# mp3412-boost-driver-17mm-mk-2_0.net
KiCad netlist of a schematic drawn in EAGLE
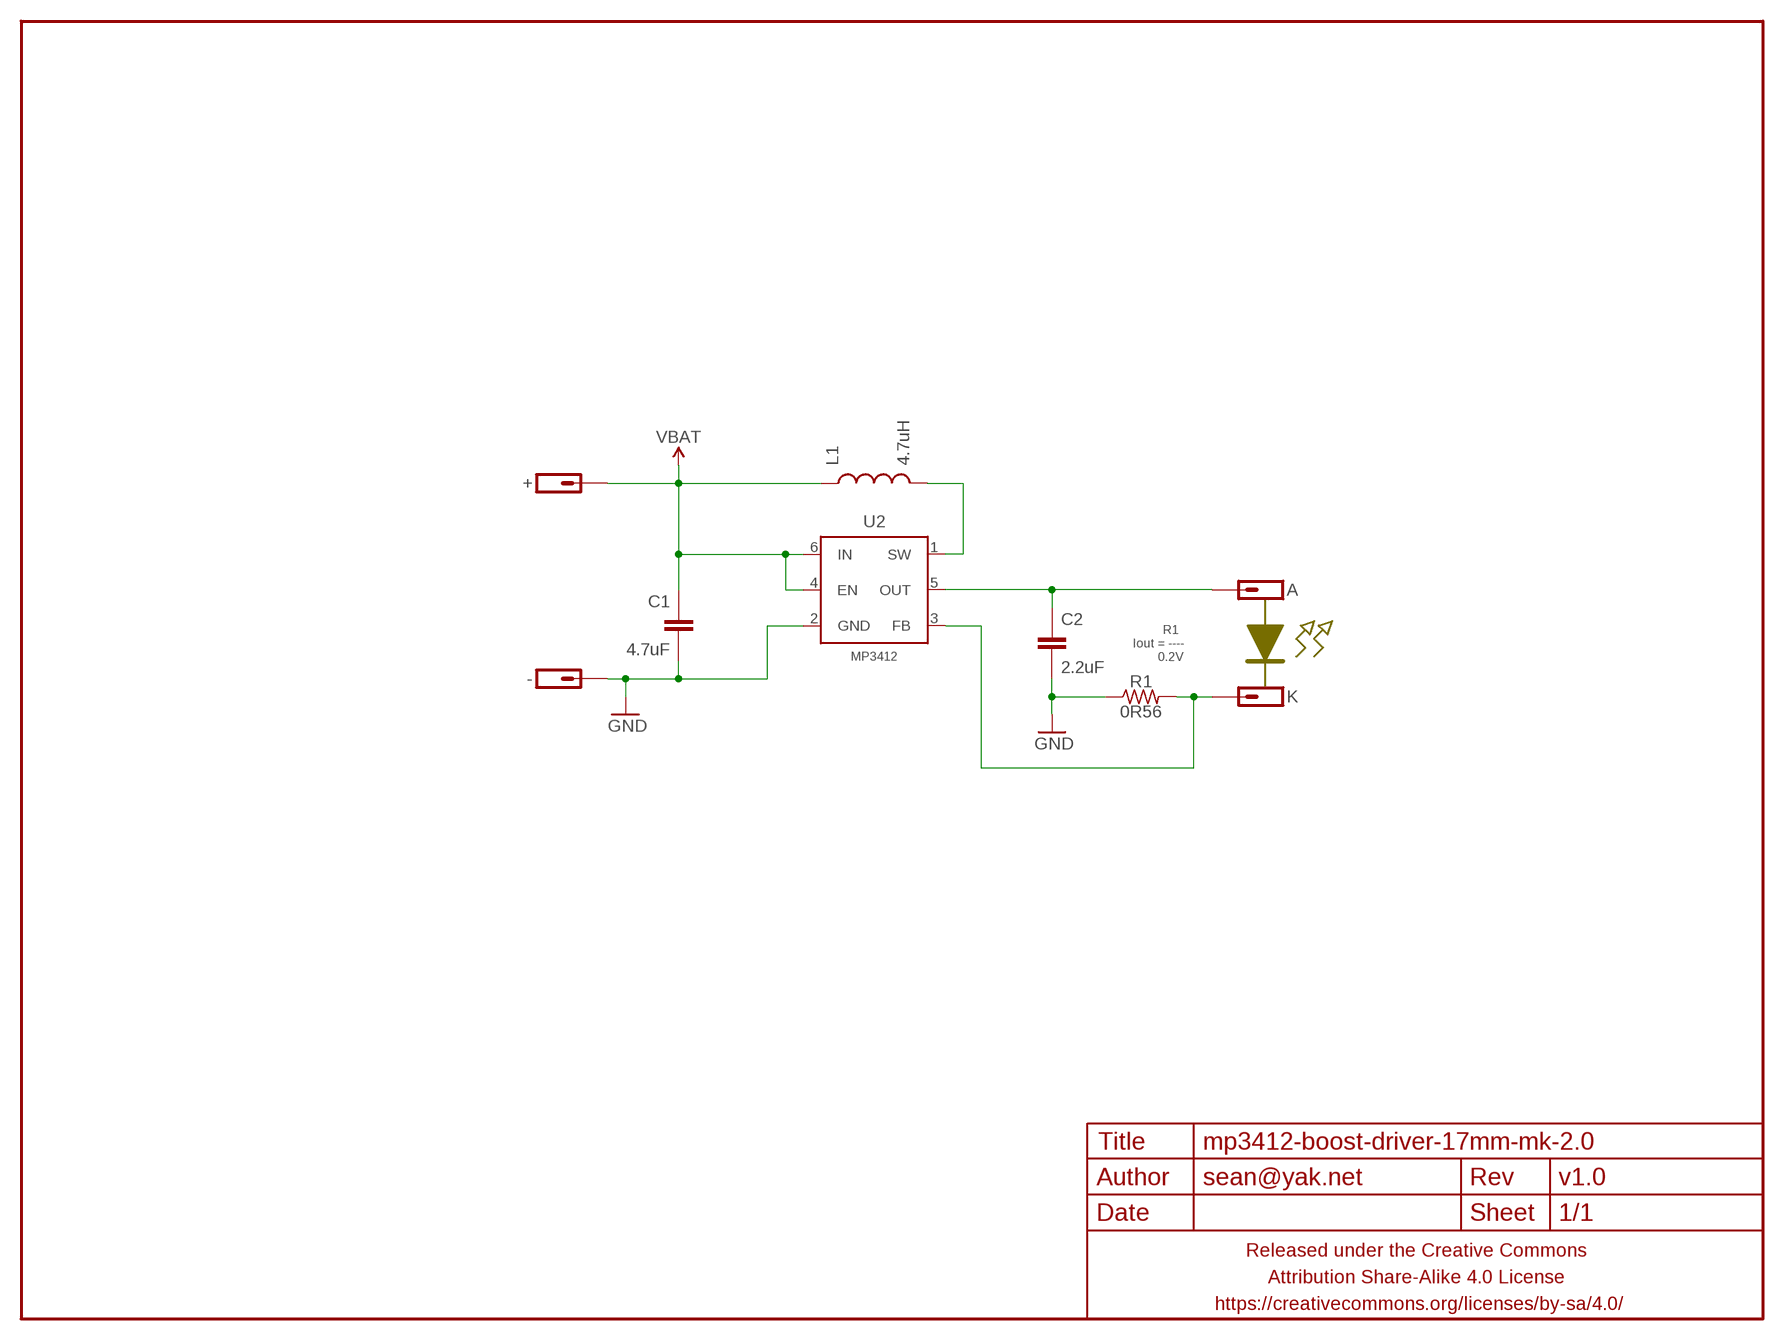
[diagram p0: schematic, sheet 1]

(export (version "E")
  (design (tool "Eeschema 10.0.6"))
  (components
    (comp (ref "+")
      (value "M01NOT-A-VIA-NOPE")
      (footprint "eagle-import:1X01_NOSILK_NOSTOP")
      (libsource (lib "eagle-import") (part "M01NOT-A-VIA-NOPE"))
    )
    (comp (ref "-")
      (value "M01NOT-A-VIA-NOPE")
      (footprint "eagle-import:1X01_NOSILK_NOSTOP")
      (libsource (lib "eagle-import") (part "M01NOT-A-VIA-NOPE"))
    )
    (comp (ref "A")
      (value "M01PTH-1MM-CIR-NS")
      (footprint "eagle-import:1X01-1MM-CIR-NS")
      (libsource (lib "eagle-import") (part "M01PTH-1MM-CIR-NS"))
    )
    (comp (ref "C1")
      (value "4.7uF")
      (footprint "eagle-import:C0603-TIGHTER")
      (libsource (lib "eagle-import") (part "CAPACITOR-CERAMICC0603-TIGHTER"))
    )
    (comp (ref "C2")
      (value "2.2uF")
      (footprint "eagle-import:C0603-TIGHTER")
      (libsource (lib "eagle-import") (part "CAPACITOR-CERAMICC0603-TIGHTER"))
    )
    (comp (ref "FRAME1")
      (value "FRAME-LETTERNO_PACKAGE")
      (footprint "eagle-import:DUMMY")
      (fields (field (name "DESIGNER") "sean@yak.net") (field (name "VERSION") "v1.0"))
      (libsource (lib "eagle-import") (part "FRAME-LETTERNO_PACKAGE"))
    )
    (comp (ref "K")
      (value "M01PTH-1MM-CIR-NS")
      (footprint "eagle-import:1X01-1MM-CIR-NS")
      (libsource (lib "eagle-import") (part "M01PTH-1MM-CIR-NS"))
    )
    (comp (ref "L1")
      (value "4.7uH")
      (footprint "eagle-import:XFL4020")
      (libsource (lib "eagle-import") (part "INDUCTORXFL4020"))
    )
    (comp (ref "R1")
      (value "0R56")
      (footprint "eagle-import:R0603-TIGHTER")
      (libsource (lib "eagle-import") (part "RESISTORR0603-TIGHTER"))
    )
    (comp (ref "U2")
      (value "MP3412")
      (footprint "eagle-import:TSOT-23-6")
      (libsource (lib "eagle-import") (part "MP3412"))
    )
  )
  (nets
    (net (code "1") (name "GND") (class "Default")
      (node (ref "-") (pin "P$1") (pinfunction "1_P$1") (pintype "passive"))
      (node (ref "C1") (pin "2") (pinfunction "2_2") (pintype "passive"))
      (node (ref "C2") (pin "2") (pinfunction "2_2") (pintype "passive"))
      (node (ref "R1") (pin "1") (pinfunction "1_1") (pintype "passive"))
      (node (ref "U2") (pin "2") (pinfunction "GND_2") (pintype "bidirectional"))
    )
    (net (code "2") (name "Net-(L1-2)") (class "Default")
      (node (ref "L1") (pin "P$2") (pinfunction "2_P$2") (pintype "passive"))
      (node (ref "U2") (pin "1") (pinfunction "SW_1") (pintype "bidirectional"))
    )
    (net (code "3") (name "Net-(U2-FB)") (class "Default")
      (node (ref "K") (pin "1") (pinfunction "1_1") (pintype "passive"))
      (node (ref "R1") (pin "2") (pinfunction "2_2") (pintype "passive"))
      (node (ref "U2") (pin "3") (pinfunction "FB_3") (pintype "bidirectional"))
    )
    (net (code "4") (name "Net-(U2-OUT)") (class "Default")
      (node (ref "A") (pin "1") (pinfunction "1_1") (pintype "passive"))
      (node (ref "C2") (pin "1") (pinfunction "1_1") (pintype "passive"))
      (node (ref "U2") (pin "5") (pinfunction "OUT_5") (pintype "bidirectional"))
    )
    (net (code "5") (name "VBAT") (class "Default")
      (node (ref "+") (pin "P$1") (pinfunction "1_P$1") (pintype "passive"))
      (node (ref "C1") (pin "1") (pinfunction "1_1") (pintype "passive"))
      (node (ref "L1") (pin "P$1") (pinfunction "1_P$1") (pintype "passive"))
      (node (ref "U2") (pin "4") (pinfunction "EN_4") (pintype "bidirectional"))
      (node (ref "U2") (pin "6") (pinfunction "IN_6") (pintype "bidirectional"))
    )
  )
)
